# HEXTIr_v1.net
KiCad netlist of a schematic drawn in EAGLE
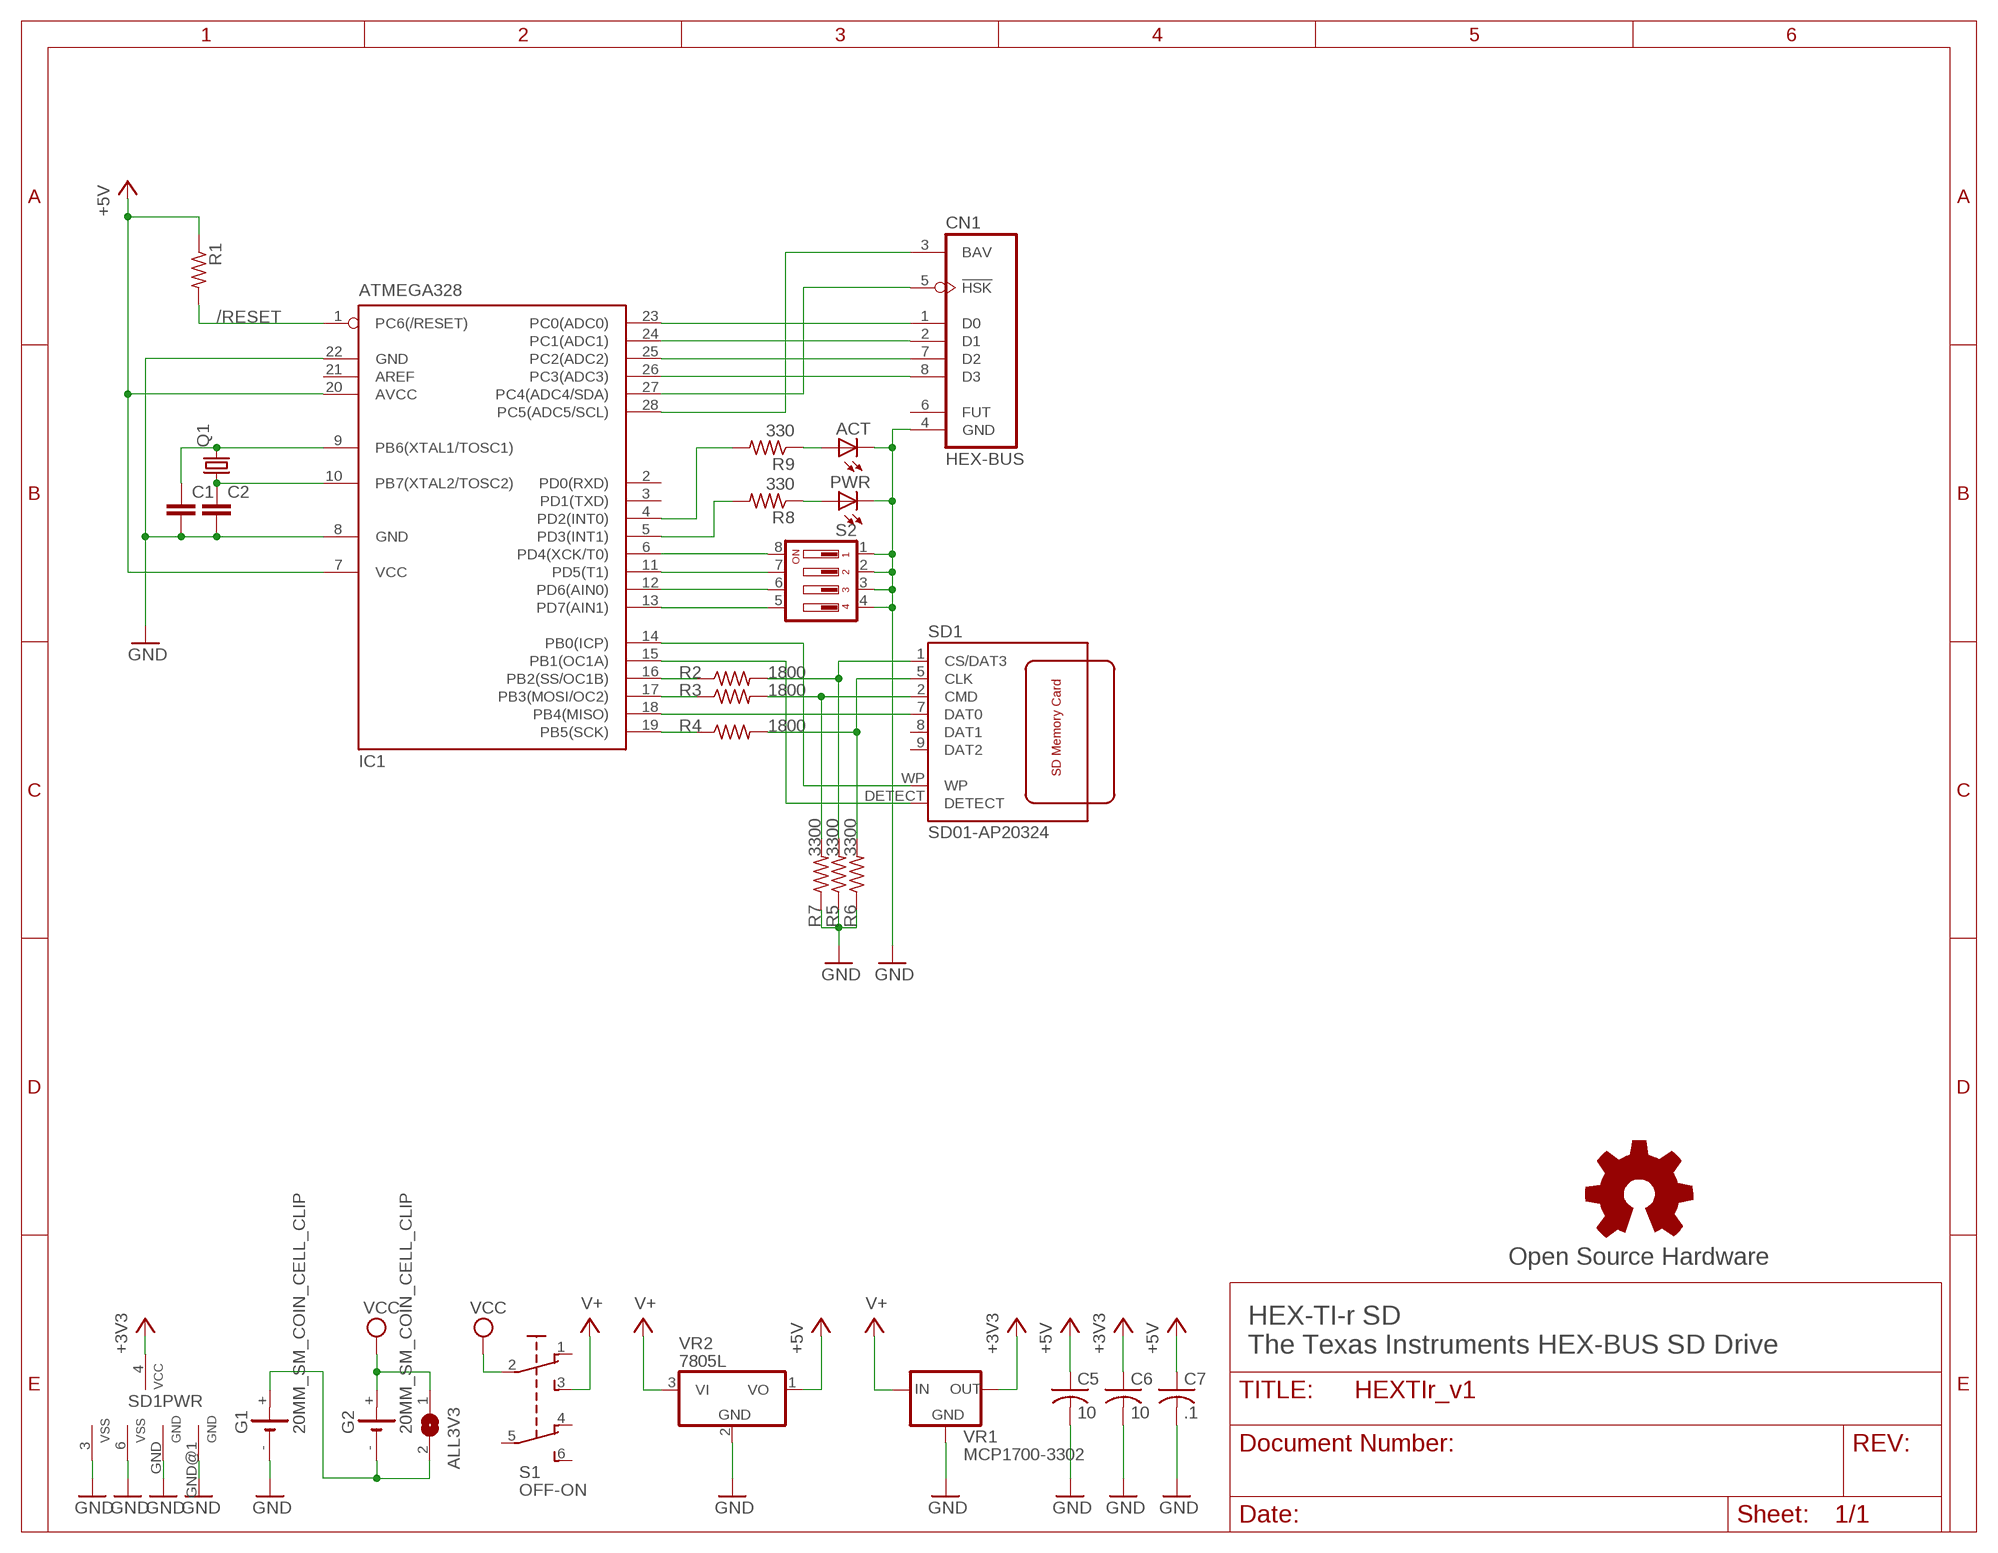
[diagram p0: schematic, sheet 1]

(export (version "E")
  (design (tool "Eeschema 10.0.6"))
  (components
    (comp (ref "ACT")
      (value "LED3MM")
      (footprint "eagle-import:LED3MM")
      (libsource (lib "eagle-import") (part "LED3MM"))
    )
    (comp (ref "ALL3V3")
      (value "SJ")
      (footprint "eagle-import:SJ")
      (libsource (lib "eagle-import") (part "SJ"))
    )
    (comp (ref "C1")
      (value "C-EU025-024X044")
      (footprint "eagle-import:C025-024X044")
      (libsource (lib "eagle-import") (part "C-EU025-024X044"))
    )
    (comp (ref "C2")
      (value "C-EU025-024X044")
      (footprint "eagle-import:C025-024X044")
      (libsource (lib "eagle-import") (part "C-EU025-024X044"))
    )
    (comp (ref "C5")
      (value "10")
      (footprint "eagle-import:C025-025X050")
      (libsource (lib "eagle-import") (part "C-US025-025X050"))
    )
    (comp (ref "C6")
      (value "10")
      (footprint "eagle-import:C025-025X050")
      (libsource (lib "eagle-import") (part "C-US025-025X050"))
    )
    (comp (ref "C7")
      (value ".1")
      (footprint "eagle-import:C025-025X050")
      (libsource (lib "eagle-import") (part "C-US025-025X050"))
    )
    (comp (ref "CN1")
      (value "HEX-BUS")
      (footprint "eagle-import:HEX-BUS")
      (libsource (lib "eagle-import") (part "HEX-BUS"))
    )
    (comp (ref "G1")
      (value "20MM_SM_COIN_CELL_CLIP")
      (footprint "eagle-import:20MM_SM_COIN_CELL_CLIP")
      (libsource (lib "eagle-import") (part "20MM_SM_COIN_CELL_CLIP"))
    )
    (comp (ref "G2")
      (value "20MM_SM_COIN_CELL_CLIP")
      (footprint "eagle-import:20MM_SM_COIN_CELL_CLIP")
      (libsource (lib "eagle-import") (part "20MM_SM_COIN_CELL_CLIP"))
    )
    (comp (ref "GOLD_ORB_SM1")
      (value "Open Source Hardware")
      (footprint "eagle-import:OSHW_5MM")
      (libsource (lib "eagle-import") (part "OSHWLOGOLOGO5MM"))
    )
    (comp (ref "IC1")
      (value "ATMEGA328")
      (footprint "eagle-import:DIL28-3")
      (libsource (lib "eagle-import") (part "MEGA8-P"))
    )
    (comp (ref "PWR")
      (value "LED3MM")
      (footprint "eagle-import:LED3MM")
      (libsource (lib "eagle-import") (part "LED3MM"))
    )
    (comp (ref "Q1")
      (value "CRYSTALHC49U-V")
      (footprint "eagle-import:HC49U-V")
      (libsource (lib "eagle-import") (part "CRYSTALHC49U-V"))
    )
    (comp (ref "R1")
      (value "R-US_0204/2V")
      (footprint "eagle-import:0204V")
      (libsource (lib "eagle-import") (part "resistor_R-US_0204/2V"))
    )
    (comp (ref "R2")
      (value "1800")
      (footprint "eagle-import:0204V")
      (libsource (lib "eagle-import") (part "R-US_0204/2V"))
    )
    (comp (ref "R3")
      (value "1800")
      (footprint "eagle-import:0204V")
      (libsource (lib "eagle-import") (part "R-US_0204/2V"))
    )
    (comp (ref "R4")
      (value "1800")
      (footprint "eagle-import:0204V")
      (libsource (lib "eagle-import") (part "R-US_0204/2V"))
    )
    (comp (ref "R5")
      (value "3300")
      (footprint "eagle-import:0204V")
      (libsource (lib "eagle-import") (part "R-US_0204/2V"))
    )
    (comp (ref "R6")
      (value "3300")
      (footprint "eagle-import:0204V")
      (libsource (lib "eagle-import") (part "R-US_0204/2V"))
    )
    (comp (ref "R7")
      (value "3300")
      (footprint "eagle-import:0204V")
      (libsource (lib "eagle-import") (part "R-US_0204/2V"))
    )
    (comp (ref "R8")
      (value "330")
      (footprint "eagle-import:0204V")
      (libsource (lib "eagle-import") (part "R-US_0204/2V"))
    )
    (comp (ref "R9")
      (value "330")
      (footprint "eagle-import:0204V")
      (libsource (lib "eagle-import") (part "R-US_0204/2V"))
    )
    (comp (ref "S1")
      (value "OFF-ON")
      (footprint "eagle-import:TINY-SLIDE")
      (libsource (lib "eagle-import") (part "TINY-SLIDE"))
    )
    (comp (ref "S2")
      (value "DP04")
      (footprint "eagle-import:DP-04")
      (libsource (lib "eagle-import") (part "DP04"))
    )
    (comp (ref "SD1")
      (value "SD01-AP20324")
      (footprint "eagle-import:SD01-AP20324")
      (libsource (lib "eagle-import") (part "SD01-AP20324"))
    )
    (comp (ref "VR1")
      (value "MCP1700-3302")
      (footprint "eagle-import:TO92")
      (libsource (lib "eagle-import") (part "MCP1700TO92"))
    )
    (comp (ref "VR2")
      (value "7805L")
      (footprint "eagle-import:TO92")
      (libsource (lib "eagle-import") (part "78L05"))
    )
  )
  (nets
    (net (code "1") (name "+3V3") (class "Default")
      (node (ref "C6") (pin "1") (pinfunction "1_1") (pintype "passive"))
      (node (ref "SD1") (pin "4") (pinfunction "3V3_4") (pintype "power_in"))
      (node (ref "VR1") (pin "3") (pinfunction "OUT_3") (pintype "passive"))
    )
    (net (code "2") (name "+5V") (class "Default")
      (node (ref "C5") (pin "1") (pinfunction "1_1") (pintype "passive"))
      (node (ref "C7") (pin "1") (pinfunction "1_1") (pintype "passive"))
      (node (ref "IC1") (pin "20") (pinfunction "AVCC_20") (pintype "power_in"))
      (node (ref "IC1") (pin "7") (pinfunction "VCC_7") (pintype "power_in"))
      (node (ref "R1") (pin "1") (pinfunction "1_1") (pintype "passive"))
      (node (ref "VR2") (pin "1") (pinfunction "VO_1") (pintype "passive"))
    )
    (net (code "3") (name "/{slash}RESET") (class "Default")
      (node (ref "IC1") (pin "1") (pinfunction "PC6(/RESET)_1") (pintype "bidirectional"))
      (node (ref "R1") (pin "2") (pinfunction "2_2") (pintype "passive"))
    )
    (net (code "4") (name "GND") (class "Default")
      (node (ref "ACT") (pin "K") (pinfunction "C_K") (pintype "passive"))
      (node (ref "C1") (pin "2") (pinfunction "2_2") (pintype "passive"))
      (node (ref "C2") (pin "2") (pinfunction "2_2") (pintype "passive"))
      (node (ref "C5") (pin "2") (pinfunction "2_2") (pintype "passive"))
      (node (ref "C6") (pin "2") (pinfunction "2_2") (pintype "passive"))
      (node (ref "C7") (pin "2") (pinfunction "2_2") (pintype "passive"))
      (node (ref "CN1") (pin "4") (pinfunction "GND_4") (pintype "power_in"))
      (node (ref "G1") (pin "-") (pinfunction "-_-") (pintype "passive"))
      (node (ref "IC1") (pin "22") (pinfunction "GND_22") (pintype "power_in"))
      (node (ref "IC1") (pin "8") (pinfunction "GND_8") (pintype "power_in"))
      (node (ref "PWR") (pin "K") (pinfunction "C_K") (pintype "passive"))
      (node (ref "R5") (pin "1") (pinfunction "1_1") (pintype "passive"))
      (node (ref "R6") (pin "1") (pinfunction "1_1") (pintype "passive"))
      (node (ref "R7") (pin "1") (pinfunction "1_1") (pintype "passive"))
      (node (ref "S2") (pin "1") (pinfunction "1_1") (pintype "passive"))
      (node (ref "S2") (pin "2") (pinfunction "2_2") (pintype "passive"))
      (node (ref "S2") (pin "3") (pinfunction "3_3") (pintype "passive"))
      (node (ref "S2") (pin "4") (pinfunction "4_4") (pintype "passive"))
      (node (ref "SD1") (pin "3") (pinfunction "VSS_3") (pintype "power_in"))
      (node (ref "SD1") (pin "6") (pinfunction "VSS_6") (pintype "power_in"))
      (node (ref "SD1") (pin "GND") (pinfunction "GND_GND") (pintype "power_in"))
      (node (ref "SD1") (pin "GND@1") (pinfunction "GND_GND@1") (pintype "power_in"))
      (node (ref "VR1") (pin "1") (pinfunction "GND_1") (pintype "input"))
      (node (ref "VR2") (pin "2") (pinfunction "GND_2") (pintype "passive"))
    )
    (net (code "5") (name "Net-(ACT-PadA)") (class "Default")
      (node (ref "ACT") (pin "A") (pinfunction "A_A") (pintype "passive"))
      (node (ref "R9") (pin "1") (pinfunction "1_1") (pintype "passive"))
    )
    (net (code "6") (name "Net-(ALL3V3-Pad2)") (class "Default")
      (node (ref "ALL3V3") (pin "2") (pinfunction "2_2") (pintype "passive"))
      (node (ref "G1") (pin "+") (pinfunction "+_+") (pintype "passive"))
      (node (ref "G2") (pin "-") (pinfunction "-_-") (pintype "passive"))
    )
    (net (code "7") (name "Net-(CN1-BAV)") (class "Default")
      (node (ref "CN1") (pin "3") (pinfunction "BAV_3") (pintype "bidirectional"))
      (node (ref "IC1") (pin "28") (pinfunction "PC5(ADC5/SCL)_28") (pintype "bidirectional"))
    )
    (net (code "8") (name "Net-(CN1-D0)") (class "Default")
      (node (ref "CN1") (pin "1") (pinfunction "D0_1") (pintype "bidirectional"))
      (node (ref "IC1") (pin "23") (pinfunction "PC0(ADC0)_23") (pintype "bidirectional"))
    )
    (net (code "9") (name "Net-(CN1-D1)") (class "Default")
      (node (ref "CN1") (pin "2") (pinfunction "D1_2") (pintype "bidirectional"))
      (node (ref "IC1") (pin "24") (pinfunction "PC1(ADC1)_24") (pintype "bidirectional"))
    )
    (net (code "10") (name "Net-(CN1-D2)") (class "Default")
      (node (ref "CN1") (pin "7") (pinfunction "D2_7") (pintype "bidirectional"))
      (node (ref "IC1") (pin "25") (pinfunction "PC2(ADC2)_25") (pintype "bidirectional"))
    )
    (net (code "11") (name "Net-(CN1-D3)") (class "Default")
      (node (ref "CN1") (pin "8") (pinfunction "D3_8") (pintype "bidirectional"))
      (node (ref "IC1") (pin "26") (pinfunction "PC3(ADC3)_26") (pintype "bidirectional"))
    )
    (net (code "12") (name "Net-(CN1-~{HSK})") (class "Default")
      (node (ref "CN1") (pin "5") (pinfunction "~{HSK}_5") (pintype "bidirectional"))
      (node (ref "IC1") (pin "27") (pinfunction "PC4(ADC4/SDA)_27") (pintype "bidirectional"))
    )
    (net (code "13") (name "Net-(IC1-PB0(ICP))") (class "Default")
      (node (ref "IC1") (pin "14") (pinfunction "PB0(ICP)_14") (pintype "bidirectional"))
      (node (ref "SD1") (pin "WP") (pinfunction "WP_WP") (pintype "passive"))
    )
    (net (code "14") (name "Net-(IC1-PB1(OC1A))") (class "Default")
      (node (ref "IC1") (pin "15") (pinfunction "PB1(OC1A)_15") (pintype "bidirectional"))
      (node (ref "SD1") (pin "DETECT") (pinfunction "DETECT_DETECT") (pintype "passive"))
    )
    (net (code "15") (name "Net-(IC1-PB2(SS{slash}OC1B))") (class "Default")
      (node (ref "IC1") (pin "16") (pinfunction "PB2(SS/OC1B)_16") (pintype "bidirectional"))
      (node (ref "R2") (pin "1") (pinfunction "1_1") (pintype "passive"))
    )
    (net (code "16") (name "Net-(IC1-PB3(MOSI{slash}OC2))") (class "Default")
      (node (ref "IC1") (pin "17") (pinfunction "PB3(MOSI/OC2)_17") (pintype "bidirectional"))
      (node (ref "R3") (pin "1") (pinfunction "1_1") (pintype "passive"))
    )
    (net (code "17") (name "Net-(IC1-PB4(MISO))") (class "Default")
      (node (ref "IC1") (pin "18") (pinfunction "PB4(MISO)_18") (pintype "bidirectional"))
      (node (ref "SD1") (pin "7") (pinfunction "DAT0_7") (pintype "passive"))
    )
    (net (code "18") (name "Net-(IC1-PB5(SCK))") (class "Default")
      (node (ref "IC1") (pin "19") (pinfunction "PB5(SCK)_19") (pintype "bidirectional"))
      (node (ref "R4") (pin "1") (pinfunction "1_1") (pintype "passive"))
    )
    (net (code "19") (name "Net-(IC1-PB6(XTAL1{slash}TOSC1))") (class "Default")
      (node (ref "C1") (pin "1") (pinfunction "1_1") (pintype "passive"))
      (node (ref "IC1") (pin "9") (pinfunction "PB6(XTAL1/TOSC1)_9") (pintype "bidirectional"))
      (node (ref "Q1") (pin "2") (pinfunction "2_2") (pintype "passive"))
    )
    (net (code "20") (name "Net-(IC1-PB7(XTAL2{slash}TOSC2))") (class "Default")
      (node (ref "C2") (pin "1") (pinfunction "1_1") (pintype "passive"))
      (node (ref "IC1") (pin "10") (pinfunction "PB7(XTAL2/TOSC2)_10") (pintype "bidirectional"))
      (node (ref "Q1") (pin "1") (pinfunction "1_1") (pintype "passive"))
    )
    (net (code "21") (name "Net-(IC1-PD2(INT0))") (class "Default")
      (node (ref "IC1") (pin "4") (pinfunction "PD2(INT0)_4") (pintype "bidirectional"))
      (node (ref "R9") (pin "2") (pinfunction "2_2") (pintype "passive"))
    )
    (net (code "22") (name "Net-(IC1-PD3(INT1))") (class "Default")
      (node (ref "IC1") (pin "5") (pinfunction "PD3(INT1)_5") (pintype "bidirectional"))
      (node (ref "R8") (pin "2") (pinfunction "2_2") (pintype "passive"))
    )
    (net (code "23") (name "Net-(IC1-PD4(XCK{slash}T0))") (class "Default")
      (node (ref "IC1") (pin "6") (pinfunction "PD4(XCK/T0)_6") (pintype "bidirectional"))
      (node (ref "S2") (pin "8") (pinfunction "8_8") (pintype "passive"))
    )
    (net (code "24") (name "Net-(IC1-PD5(T1))") (class "Default")
      (node (ref "IC1") (pin "11") (pinfunction "PD5(T1)_11") (pintype "bidirectional"))
      (node (ref "S2") (pin "7") (pinfunction "7_7") (pintype "passive"))
    )
    (net (code "25") (name "Net-(IC1-PD6(AIN0))") (class "Default")
      (node (ref "IC1") (pin "12") (pinfunction "PD6(AIN0)_12") (pintype "bidirectional"))
      (node (ref "S2") (pin "6") (pinfunction "6_6") (pintype "passive"))
    )
    (net (code "26") (name "Net-(IC1-PD7(AIN1))") (class "Default")
      (node (ref "IC1") (pin "13") (pinfunction "PD7(AIN1)_13") (pintype "bidirectional"))
      (node (ref "S2") (pin "5") (pinfunction "5_5") (pintype "passive"))
    )
    (net (code "27") (name "Net-(PWR-PadA)") (class "Default")
      (node (ref "PWR") (pin "A") (pinfunction "A_A") (pintype "passive"))
      (node (ref "R8") (pin "1") (pinfunction "1_1") (pintype "passive"))
    )
    (net (code "28") (name "Net-(SD1A-CLK)") (class "Default")
      (node (ref "R4") (pin "2") (pinfunction "2_2") (pintype "passive"))
      (node (ref "R6") (pin "2") (pinfunction "2_2") (pintype "passive"))
      (node (ref "SD1") (pin "5") (pinfunction "CLK_5") (pintype "passive"))
    )
    (net (code "29") (name "Net-(SD1A-CMD)") (class "Default")
      (node (ref "R3") (pin "2") (pinfunction "2_2") (pintype "passive"))
      (node (ref "R7") (pin "2") (pinfunction "2_2") (pintype "passive"))
      (node (ref "SD1") (pin "2") (pinfunction "CMD_2") (pintype "passive"))
    )
    (net (code "30") (name "Net-(SD1A-CS{slash}DAT3)") (class "Default")
      (node (ref "R2") (pin "2") (pinfunction "2_2") (pintype "passive"))
      (node (ref "R5") (pin "2") (pinfunction "2_2") (pintype "passive"))
      (node (ref "SD1") (pin "1") (pinfunction "CS/DAT3_1") (pintype "passive"))
    )
    (net (code "31") (name "V+") (class "Default")
      (node (ref "S1") (pin "3") (pinfunction "S_3") (pintype "passive"))
      (node (ref "VR1") (pin "2") (pinfunction "IN_2") (pintype "input"))
      (node (ref "VR2") (pin "3") (pinfunction "VI_3") (pintype "input"))
    )
    (net (code "32") (name "VCC") (class "Default")
      (node (ref "ALL3V3") (pin "1") (pinfunction "1_1") (pintype "passive"))
      (node (ref "G2") (pin "+") (pinfunction "+_+") (pintype "passive"))
      (node (ref "S1") (pin "2") (pinfunction "P_2") (pintype "passive"))
    )
    (net (code "33") (name "unconnected-(CN1-FUT-Pad6)") (class "Default")
      (node (ref "CN1") (pin "6") (pinfunction "FUT_6") (pintype "passive"))
    )
    (net (code "34") (name "unconnected-(IC1-AREF-Pad21)") (class "Default")
      (node (ref "IC1") (pin "21") (pinfunction "AREF_21") (pintype "passive"))
    )
    (net (code "35") (name "unconnected-(IC1-PD0(RXD)-Pad2)") (class "Default")
      (node (ref "IC1") (pin "2") (pinfunction "PD0(RXD)_2") (pintype "bidirectional"))
    )
    (net (code "36") (name "unconnected-(IC1-PD1(TXD)-Pad3)") (class "Default")
      (node (ref "IC1") (pin "3") (pinfunction "PD1(TXD)_3") (pintype "bidirectional"))
    )
    (net (code "37") (name "unconnected-(S1-O-Pad1)") (class "Default")
      (node (ref "S1") (pin "1") (pinfunction "O_1") (pintype "passive"))
    )
    (net (code "38") (name "unconnected-(S1-O1-Pad4)") (class "Default")
      (node (ref "S1") (pin "4") (pinfunction "O1_4") (pintype "passive"))
    )
    (net (code "39") (name "unconnected-(S1-P1-Pad5)") (class "Default")
      (node (ref "S1") (pin "5") (pinfunction "P1_5") (pintype "passive"))
    )
    (net (code "40") (name "unconnected-(S1-S1-Pad6)") (class "Default")
      (node (ref "S1") (pin "6") (pinfunction "S1_6") (pintype "passive"))
    )
    (net (code "41") (name "unconnected-(SD1A-DAT1-Pad8)") (class "Default")
      (node (ref "SD1") (pin "8") (pinfunction "DAT1_8") (pintype "passive"))
    )
    (net (code "42") (name "unconnected-(SD1A-DAT2-Pad9)") (class "Default")
      (node (ref "SD1") (pin "9") (pinfunction "DAT2_9") (pintype "passive"))
    )
  )
)
